# Audio_Input_Mic_Array.net
KiCad netlist of a schematic drawn in Altium Designer
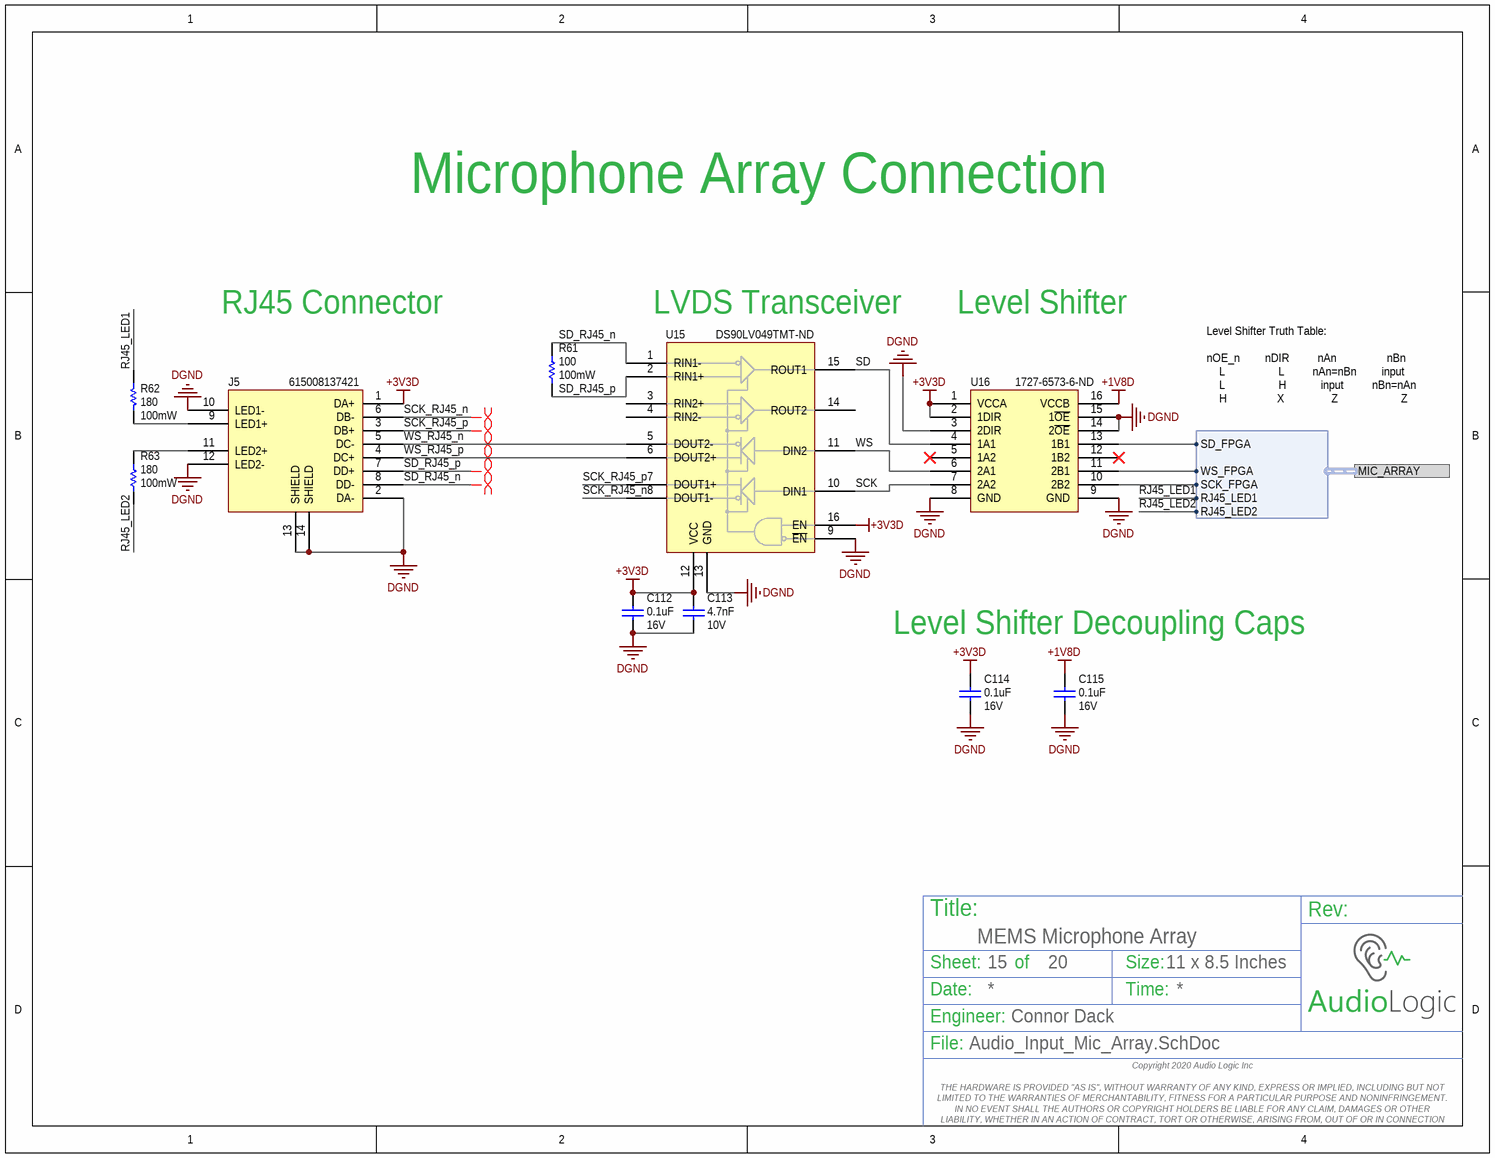
[diagram p0: Audio_Input_Mic_Array.SchDoc]

(export (version "E")
  (design (tool "Eeschema 10.0.6"))
  (components
    (comp (ref "C112")
      (value "CL10F104ZO8NNNC")
      (footprint "3-0603_L")
      (description "CAP CER 0.1UF 16V Y5V 0603")
      (fields
        (field (name "MANUFACTURER") "Samsung")
        (field (name "TOLERANCE") "80%")
        (field (name "VOLTAGE RATING") "16V")
        (field (name "CAPACITANCE") "0.1uF")
      )
      (libsource (lib "Schematic_Components_CD") (part "CL10F104ZO8NNNC"))
    )
    (comp (ref "C113")
      (value "C0603C472K8RACTU")
      (footprint "3-0603_L")
      (description "CAP CER 4700PF 10V X7R 0603")
      (fields
        (field (name "MANUFACTURER") "KEMET")
        (field (name "VOLTAGE RATING") "10V")
        (field (name "TOLERANCE") "10%")
        (field (name "CAPACITANCE") "4.7nF")
      )
      (libsource (lib "Schematic_Components_CD") (part "C0603C472K8RACTU"))
    )
    (comp (ref "C114")
      (value "CL10F104ZO8NNNC")
      (footprint "3-0603_L")
      (description "CAP CER 0.1UF 16V Y5V 0603")
      (fields
        (field (name "MANUFACTURER") "Samsung")
        (field (name "TOLERANCE") "80%")
        (field (name "VOLTAGE RATING") "16V")
        (field (name "CAPACITANCE") "0.1uF")
      )
      (libsource (lib "Schematic_Components_CD") (part "CL10F104ZO8NNNC"))
    )
    (comp (ref "C115")
      (value "CL10F104ZO8NNNC")
      (footprint "3-0603_L")
      (description "CAP CER 0.1UF 16V Y5V 0603")
      (fields
        (field (name "MANUFACTURER") "Samsung")
        (field (name "TOLERANCE") "80%")
        (field (name "VOLTAGE RATING") "16V")
        (field (name "CAPACITANCE") "0.1uF")
      )
      (libsource (lib "Schematic_Components_CD") (part "CL10F104ZO8NNNC"))
    )
    (comp (ref "J5")
      (value "CONN MOD JACK 8P8C R/A SHIELDED")
      (footprint "RJ45")
      (description "Jack Modular Connector 8p8c (RJ45, Ethernet) 90° Angle (Right) Shielded, EMI Finger Cat5")
      (fields
        (field (name "MANUFACTURER") "Wurth Electronics")
        (field (name "MANUFACTURER PART NUMBER") "615008137421")
      )
      (libsource (lib "Schematic_Components_CD") (part "615008137421"))
    )
    (comp (ref "R61")
      (value "ERA-3AEB101V")
      (footprint "3-0603_R_L")
      (description "RES SMD 100 OHM 0.1% 1/10W 0603")
      (fields
        (field (name "MANUFACTURER") "Panasonic ECG")
        (field (name "POWER RATING") "100mW")
        (field (name "TOLERANCE") "0.1%")
        (field (name "RESISTANCE") "100")
      )
      (libsource (lib "Schematic_Components_CD") (part "ERA-3AEB101V"))
    )
    (comp (ref "R62")
      (value "ERA-3AEB181V")
      (footprint "3-0603_R_L")
      (description "RES SMD 180 OHM 0.1% 1/10W 0603")
      (fields
        (field (name "MANUFACTURER") "Panasonic")
        (field (name "MANUFACTURER PART NUMBER") "ERA3AEB181V")
        (field (name "POWER RATING") "100mW")
        (field (name "RESISTANCE") "180")
      )
      (libsource (lib "Schematic_Components_CD") (part "ERA-3AEB181V"))
    )
    (comp (ref "R63")
      (value "ERA-3AEB181V")
      (footprint "3-0603_R_L")
      (description "RES SMD 180 OHM 0.1% 1/10W 0603")
      (fields
        (field (name "MANUFACTURER") "Panasonic")
        (field (name "MANUFACTURER PART NUMBER") "ERA3AEB181V")
        (field (name "POWER RATING") "100mW")
        (field (name "RESISTANCE") "180")
      )
      (libsource (lib "Schematic_Components_CD") (part "ERA-3AEB181V"))
    )
    (comp (ref "U15")
      (value "DS90LV049TMT")
      (footprint "TSOP65P640X120-16N")
      (description "IC LDVR/RCVR PAIR LVDS 16TSSOP")
      (fields
        (field (name "MANUFACTURER") "TI National Semiconductor")
        (field (name "SUPPLIER PART NUMBER 1") "DS90LV049TMT-ND")
      )
      (libsource (lib "Schematic_Components_CD") (part "DS90LV049TMT"))
    )
    (comp (ref "U16")
      (value "IC TXRX 4BIT DUAL 3ST 16TSSOP")
      (footprint "TSOP65P640X120-16N")
      (description "Voltage Level Translator Bidirectional 2 Circuit 2 Channel 380Mbps 16-TSSOP")
      (fields
        (field (name "MANUFACTURER") "NXP Semiconductors")
        (field (name "SUPPLIER PART NUMBER 1") "1727-6573-6-ND")
        (field (name "MANUFACTURER PART NUMBER") "74AVC4T245PW,118")
      )
      (libsource (lib "Schematic_Components_CD") (part "74AVC4T245PW,118"))
    )
  )
  (nets
    (net (code "3") (name "+1V8D") (class "Default")
      (node (ref "C115") (pin "1") (pinfunction "1_1") (pintype "passive"))
      (node (ref "U16") (pin "16") (pinfunction "VCCB_16") (pintype "passive"))
    )
    (net (code "4") (name "+3V3D") (class "Default")
      (node (ref "C112") (pin "1") (pinfunction "1_1") (pintype "passive"))
      (node (ref "C113") (pin "2") (pinfunction "2_2") (pintype "passive"))
      (node (ref "C114") (pin "1") (pinfunction "1_1") (pintype "passive"))
      (node (ref "J5") (pin "1") (pinfunction "DA+_1") (pintype "passive"))
      (node (ref "U15") (pin "12") (pinfunction "VCC_12") (pintype "power_in"))
      (node (ref "U15") (pin "16") (pinfunction "EN_16") (pintype "passive"))
      (node (ref "U16") (pin "1") (pinfunction "VCCA_1") (pintype "passive"))
      (node (ref "U16") (pin "2") (pinfunction "1DIR_2") (pintype "passive"))
    )
    (net (code "5") (name "/RJ45_LED1") (class "Default")
      (node (ref "R62") (pin "1") (pinfunction "1_1") (pintype "passive"))
    )
    (net (code "6") (name "/RJ45_LED2") (class "Default")
      (node (ref "R63") (pin "1") (pinfunction "1_1") (pintype "passive"))
    )
    (net (code "7") (name "/SCK") (class "Default")
      (node (ref "U15") (pin "10") (pinfunction "DIN1_10") (pintype "passive"))
      (node (ref "U16") (pin "7") (pinfunction "2A2_7") (pintype "passive"))
    )
    (net (code "8") (name "/SCK_FPGA") (class "Default")
      (node (ref "U16") (pin "10") (pinfunction "2B2_10") (pintype "passive"))
    )
    (net (code "9") (name "/SCK_RJ45_n") (class "Default")
      (node (ref "J5") (pin "6") (pinfunction "DB-_6") (pintype "passive"))
      (node (ref "U15") (pin "8") (pinfunction "DOUT1-_8") (pintype "passive"))
    )
    (net (code "10") (name "/SCK_RJ45_p") (class "Default")
      (node (ref "J5") (pin "3") (pinfunction "DB+_3") (pintype "passive"))
      (node (ref "U15") (pin "7") (pinfunction "DOUT1+_7") (pintype "passive"))
    )
    (net (code "11") (name "/SD") (class "Default")
      (node (ref "U15") (pin "15") (pinfunction "ROUT1_15") (pintype "passive"))
      (node (ref "U16") (pin "4") (pinfunction "1A1_4") (pintype "passive"))
    )
    (net (code "12") (name "/SD_FPGA") (class "Default")
      (node (ref "U16") (pin "13") (pinfunction "1B1_13") (pintype "passive"))
    )
    (net (code "13") (name "/SD_RJ45_n") (class "Default")
      (node (ref "J5") (pin "8") (pinfunction "DD-_8") (pintype "passive"))
      (node (ref "R61") (pin "2") (pinfunction "2_2") (pintype "passive"))
      (node (ref "U15") (pin "1") (pinfunction "RIN1-_1") (pintype "passive"))
    )
    (net (code "14") (name "/SD_RJ45_p") (class "Default")
      (node (ref "J5") (pin "7") (pinfunction "DD+_7") (pintype "passive"))
      (node (ref "R61") (pin "1") (pinfunction "1_1") (pintype "passive"))
      (node (ref "U15") (pin "2") (pinfunction "RIN1+_2") (pintype "passive"))
    )
    (net (code "15") (name "/WS") (class "Default")
      (node (ref "U15") (pin "11") (pinfunction "DIN2_11") (pintype "passive"))
      (node (ref "U16") (pin "6") (pinfunction "2A1_6") (pintype "passive"))
    )
    (net (code "16") (name "/WS_FPGA") (class "Default")
      (node (ref "U16") (pin "11") (pinfunction "2B1_11") (pintype "passive"))
    )
    (net (code "17") (name "/WS_RJ45_n") (class "Default")
      (node (ref "J5") (pin "5") (pinfunction "DC-_5") (pintype "passive"))
      (node (ref "U15") (pin "5") (pinfunction "DOUT2-_5") (pintype "passive"))
    )
    (net (code "18") (name "/WS_RJ45_p") (class "Default")
      (node (ref "J5") (pin "4") (pinfunction "DC+_4") (pintype "passive"))
      (node (ref "U15") (pin "6") (pinfunction "DOUT2+_6") (pintype "passive"))
    )
    (net (code "20") (name "DGND") (class "Default")
      (node (ref "C112") (pin "2") (pinfunction "2_2") (pintype "passive"))
      (node (ref "C113") (pin "1") (pinfunction "1_1") (pintype "passive"))
      (node (ref "C114") (pin "2") (pinfunction "2_2") (pintype "passive"))
      (node (ref "C115") (pin "2") (pinfunction "2_2") (pintype "passive"))
      (node (ref "J5") (pin "10") (pinfunction "LED1-_10") (pintype "passive"))
      (node (ref "J5") (pin "12") (pinfunction "LED2-_12") (pintype "passive"))
      (node (ref "J5") (pin "13") (pinfunction "SHIELD_13") (pintype "passive"))
      (node (ref "J5") (pin "14") (pinfunction "SHIELD_14") (pintype "passive"))
      (node (ref "J5") (pin "2") (pinfunction "DA-_2") (pintype "passive"))
      (node (ref "U15") (pin "13") (pinfunction "GND_13") (pintype "power_in"))
      (node (ref "U15") (pin "9") (pinfunction "~{EN}_9") (pintype "passive"))
      (node (ref "U16") (pin "14") (pinfunction "2~{OE}_14") (pintype "passive"))
      (node (ref "U16") (pin "15") (pinfunction "1~{OE}_15") (pintype "passive"))
      (node (ref "U16") (pin "3") (pinfunction "2DIR_3") (pintype "passive"))
      (node (ref "U16") (pin "8") (pinfunction "GND_8") (pintype "passive"))
      (node (ref "U16") (pin "9") (pinfunction "GND_9") (pintype "passive"))
    )
    (net (code "21") (name "Net-(J5-LED1+)") (class "Default")
      (node (ref "J5") (pin "9") (pinfunction "LED1+_9") (pintype "passive"))
      (node (ref "R62") (pin "2") (pinfunction "2_2") (pintype "passive"))
    )
    (net (code "22") (name "Net-(J5-LED2+)") (class "Default")
      (node (ref "J5") (pin "11") (pinfunction "LED2+_11") (pintype "passive"))
      (node (ref "R63") (pin "2") (pinfunction "2_2") (pintype "passive"))
    )
    (net (code "23") (name "unconnected-(U15-RIN2+-Pad3)") (class "Default")
      (node (ref "U15") (pin "3") (pinfunction "RIN2+_3") (pintype "passive"))
    )
    (net (code "24") (name "unconnected-(U15-RIN2--Pad4)") (class "Default")
      (node (ref "U15") (pin "4") (pinfunction "RIN2-_4") (pintype "passive"))
    )
    (net (code "25") (name "unconnected-(U15-ROUT2-Pad14)") (class "Default")
      (node (ref "U15") (pin "14") (pinfunction "ROUT2_14") (pintype "passive"))
    )
    (net (code "26") (name "unconnected-(U16-1A2-Pad5)") (class "Default")
      (node (ref "U16") (pin "5") (pinfunction "1A2_5") (pintype "passive+no_connect"))
    )
    (net (code "27") (name "unconnected-(U16-1B2-Pad12)") (class "Default")
      (node (ref "U16") (pin "12") (pinfunction "1B2_12") (pintype "passive+no_connect"))
    )
  )
)
